# LoraSTM32.net
KiCad netlist of a schematic drawn in Altium Designer
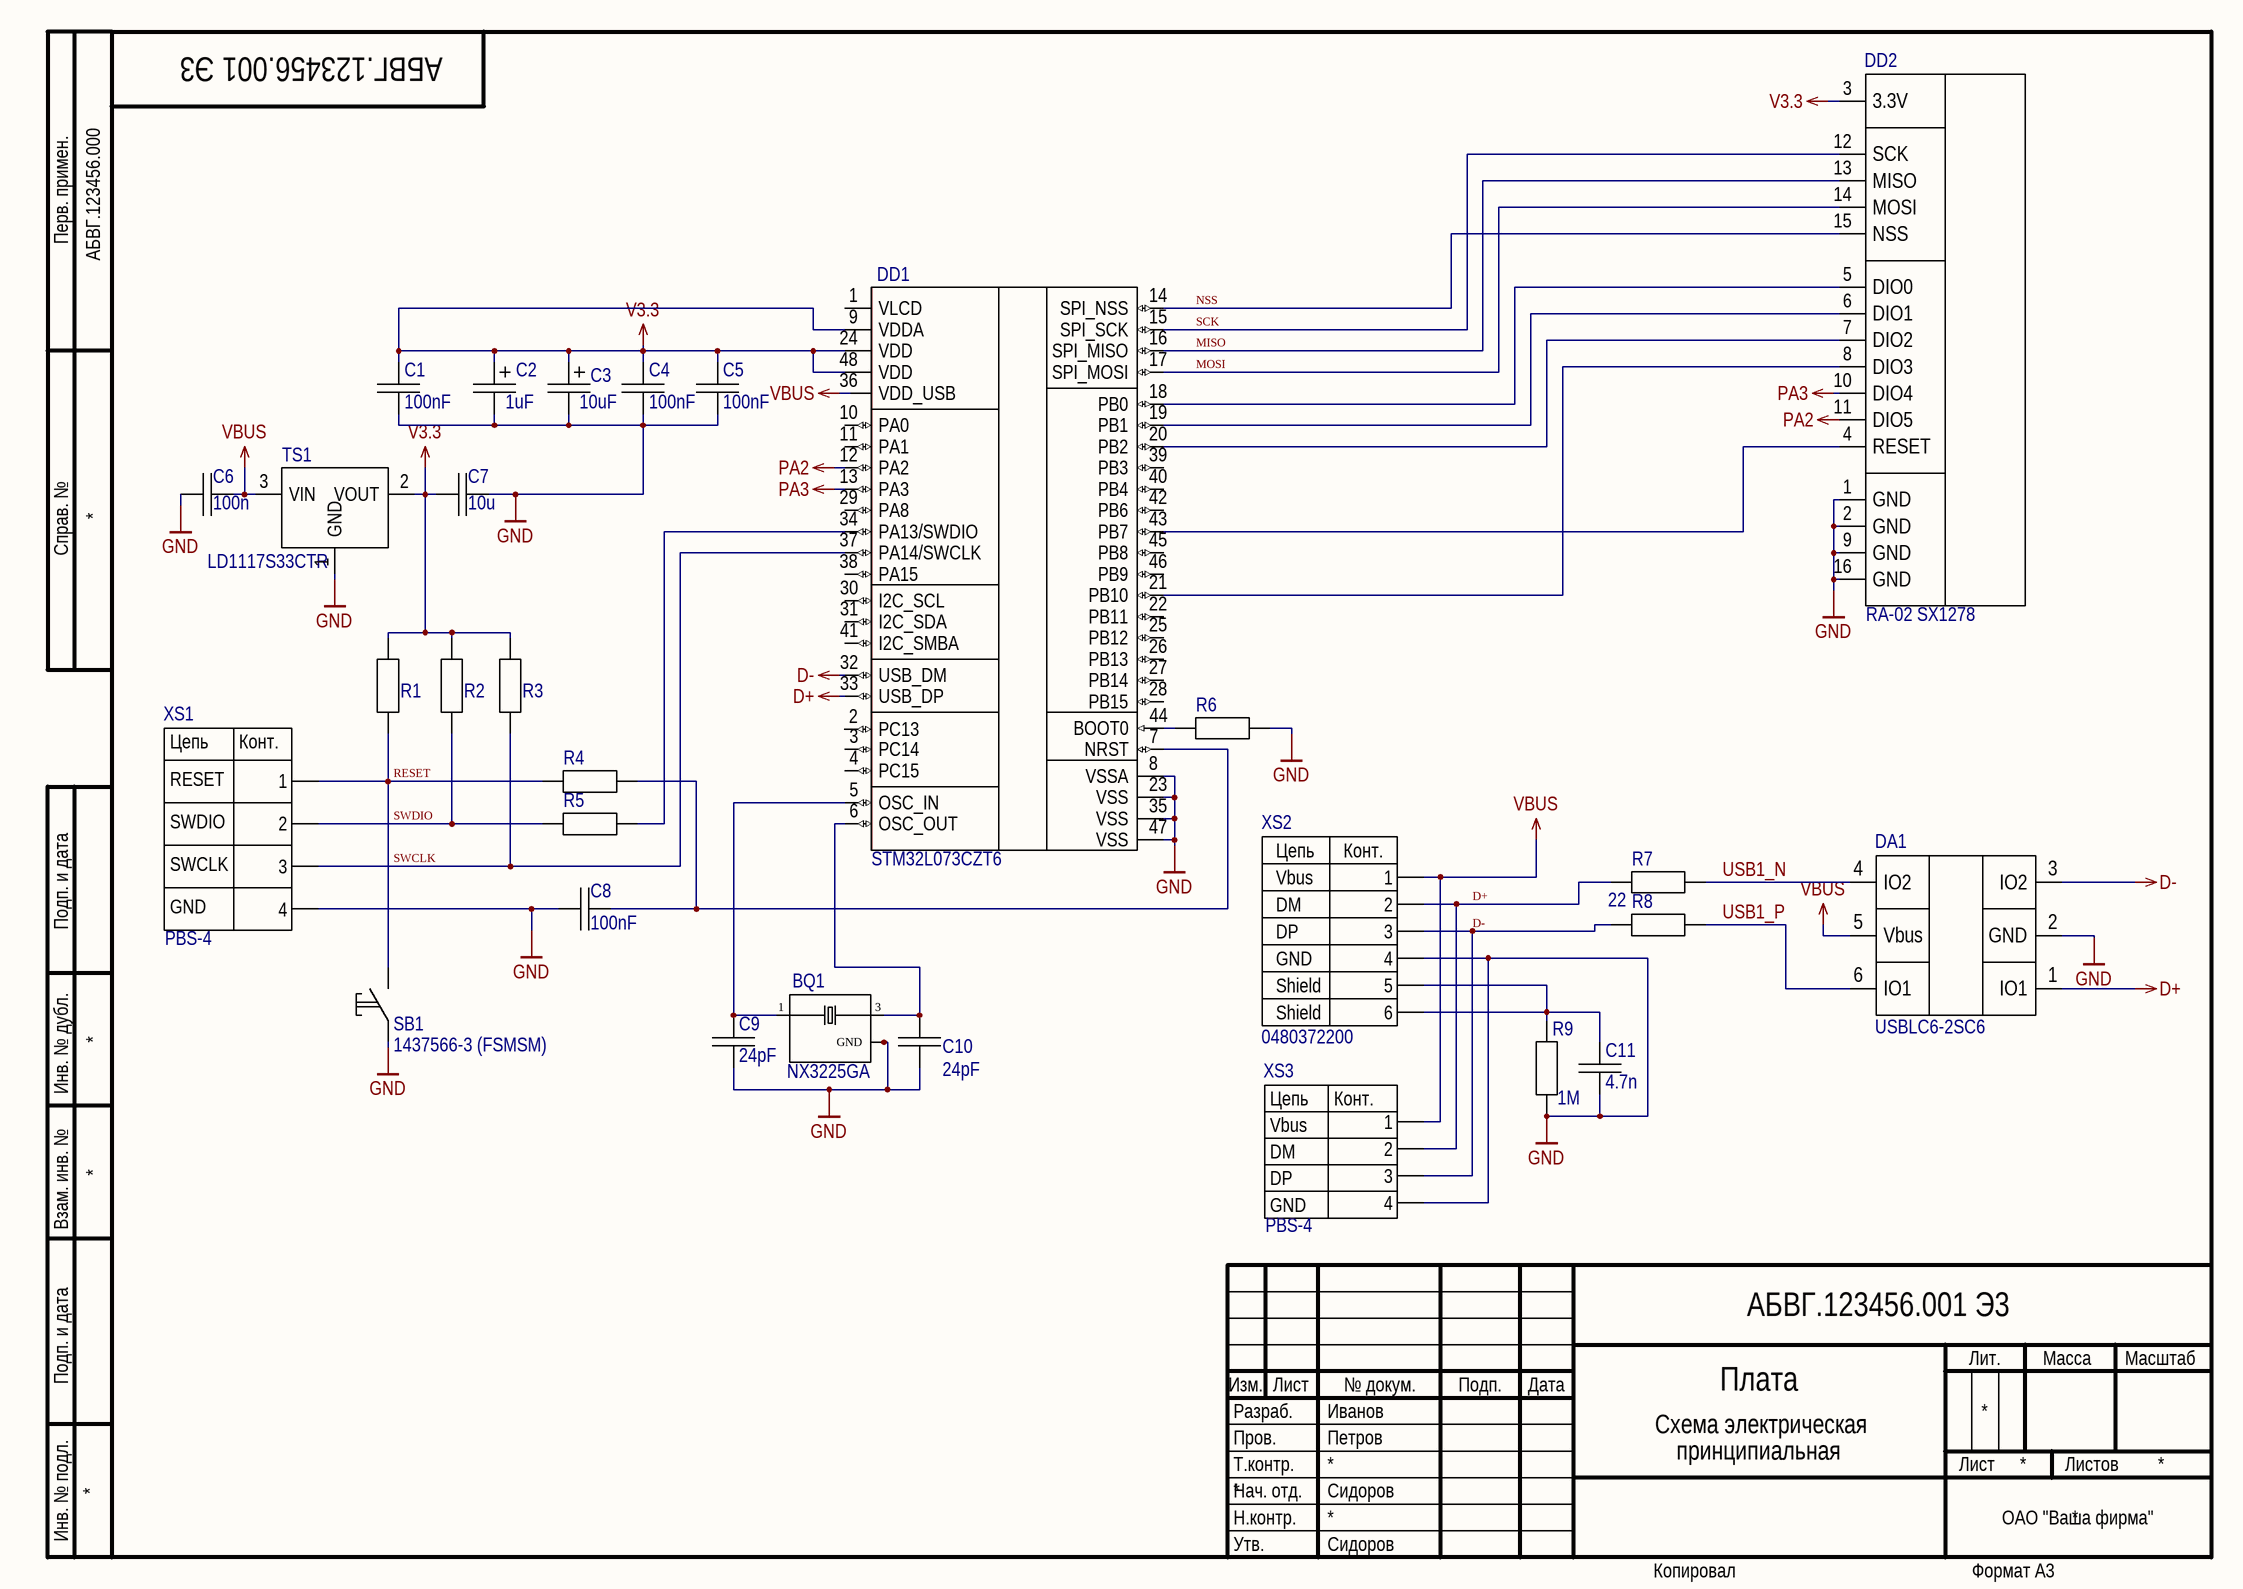
[diagram p0: LoraSTM32.SchDoc]

(export (version "E")
  (design (tool "Eeschema 10.0.6"))
  (components
    (comp (ref "BQ1")
      (value "NX3225GA")
      (footprint "NDK_NX3225GA_0")
      (description "NX3225GA-25MHZ 8pF, 25 МГц, 30/20ppm, 8пФ, -40...+85°C, SMD 3.2*2.5*0.75мм, Кварцевый резонатор")
      (fields (field (name "MF") "NDK America, Inc.") (field (name "MP") "NX3225GA-25MHZ 8pF"))
      (libsource (lib "godnota") (part "NX3225GA-25MHZ"))
    )
    (comp (ref "C1")
      (value "*")
      (footprint "CAPC1608X09L")
      (description "Конденсатор 1.6x0.8 мм")
      (fields (field (name "TOLERANCE") "±10%") (field (name "GRM188R71H104K") "100nF"))
      (libsource (lib "RPSLib") (part "CC1608"))
    )
    (comp (ref "C2")
      (value "*")
      (footprint "CAPMP3216X16N-A")
      (description "Tantalum Surface Mount Capacitor, Size A")
      (fields (field (name "TECAP1/16VA10") "1uF") (field (name "VOLTAGE") "6.3V"))
      (libsource (lib "RPSLib") (part "CT3216-A"))
    )
    (comp (ref "C3")
      (value "*")
      (footprint "CAPMP3216X16N-A")
      (description "Tantalum Surface Mount Capacitor, Size A")
      (fields (field (name "TECAP10/10VA10") "10uF") (field (name "VOLTAGE") "6.3V"))
      (libsource (lib "RPSLib") (part "CT3216-A"))
    )
    (comp (ref "C4")
      (value "GRM188R72A104KA35D")
      (footprint "CAPC1608X09L")
      (description "Конденсатор 1.6x0.8 мм")
      (fields (field (name "TOLERANCE") "±10%") (field (name "GRM188R71H104K") "100nF"))
      (libsource (lib "RPSLib") (part "CC1608"))
    )
    (comp (ref "C5")
      (value "*")
      (footprint "CAPC1608X09L")
      (description "Конденсатор 1.6x0.8 мм")
      (fields (field (name "TOLERANCE") "±10%") (field (name "GRM188R71H104K") "100nF"))
      (libsource (lib "RPSLib") (part "CC1608"))
    )
    (comp (ref "C6")
      (value "*")
      (footprint "CAPC1608X09L")
      (description "Конденсатор 1.6x0.8 мм")
      (fields (field (name "TOLERANCE") "±10%") (field (name "GRM188R71H104K") "100n"))
      (libsource (lib "RPSLib") (part "CC1608"))
    )
    (comp (ref "C7")
      (value "*")
      (footprint "CAPC1608X09L")
      (description "Конденсатор 1.6x0.8 мм")
      (fields (field (name "TOLERANCE") "±10%") (field (name "GRM188R61E106M") "10u"))
      (libsource (lib "RPSLib") (part "CC1608"))
    )
    (comp (ref "C8")
      (value "*")
      (footprint "CAPC1608X09L")
      (description "Конденсатор 1.6x0.8 мм")
      (fields (field (name "TOLERANCE") "±10%") (field (name "GRM188R71H104K") "100nF"))
      (libsource (lib "RPSLib") (part "CC1608"))
    )
    (comp (ref "C9")
      (value "*")
      (footprint "CAPC1608X09L")
      (description "Конденсатор 1.6x0.8 мм")
      (fields (field (name "TOLERANCE") "±10%") (field (name "GRM1885C1H240J") "24pF"))
      (libsource (lib "RPSLib") (part "CC1608"))
    )
    (comp (ref "C10")
      (value "*")
      (footprint "CAPC1608X09L")
      (description "Конденсатор 1.6x0.8 мм")
      (fields (field (name "TOLERANCE") "±10%") (field (name "GRM1887U1H472JA01D") "24pF"))
      (libsource (lib "RPSLib") (part "CC1608"))
    )
    (comp (ref "C11")
      (value "4.7n")
      (footprint "CAPC1608X09L")
      (description "Конденсатор 1.6x0.8 мм")
      (fields (field (name "TOLERANCE") "±10%"))
      (libsource (lib "RPSLib") (part "CC1608"))
    )
    (comp (ref "DA1")
      (value "USBLC6-2SC6")
      (footprint "SOT95P280X145-6N")
      (description "USB protection IC")
      (fields (field (name "MANUFACTURER") "STMicroelectronics"))
      (libsource (lib "RPSLib") (part "USBLC6-2SC6"))
    )
    (comp (ref "DD1")
      (value "STM32L073CZT6")
      (footprint "*QFP50P900X900X160-48N")
      (description "ARMВ® CortexВ®-M0+ STM32 L0 Microcontroller IC 32-Bit 32MHz 192KB _192K x 8_ FLASH 48-LQFP")
      (fields (field (name "MF") "STMicroelectronics") (field (name "DIGI-KEY_PART_NUMBER") "497-17506-ND"))
      (libsource (lib "godnota") (part "STM32L073CZT6"))
    )
    (comp (ref "DD2") (value "RA-02 SX1278") (footprint "RA-02") (libsource (lib "RA-02") (part "RA-02")))
    (comp (ref "R1")
      (value "R1608")
      (footprint "RESC1608X05N")
      (description "Резистор 1.6x0.8 мм")
      (fields (field (name "TOLERANCE") "±1%"))
      (libsource (lib "RPSLib") (part "R1608"))
    )
    (comp (ref "R2")
      (value "R1608")
      (footprint "RESC1608X05N")
      (description "Резистор 1.6x0.8 мм")
      (fields (field (name "TOLERANCE") "±1%"))
      (libsource (lib "RPSLib") (part "R1608"))
    )
    (comp (ref "R3")
      (value "R1608")
      (footprint "RESC1608X05N")
      (description "Резистор 1.6x0.8 мм")
      (fields (field (name "TOLERANCE") "±1%"))
      (libsource (lib "RPSLib") (part "R1608"))
    )
    (comp (ref "R4")
      (value "R1608")
      (footprint "RESC1608X05N")
      (description "Резистор 1.6x0.8 мм")
      (fields (field (name "TOLERANCE") "±1%"))
      (libsource (lib "RPSLib") (part "R1608"))
    )
    (comp (ref "R5")
      (value "R1608")
      (footprint "RESC1608X05N")
      (description "Резистор 1.6x0.8 мм")
      (fields (field (name "TOLERANCE") "±1%"))
      (libsource (lib "RPSLib") (part "R1608"))
    )
    (comp (ref "R6")
      (value "R1608")
      (footprint "RESC1608X05N")
      (description "Резистор 1.6x0.8 мм")
      (fields (field (name "TOLERANCE") "±1%"))
      (libsource (lib "RPSLib") (part "R1608"))
    )
    (comp (ref "R7")
      (value "R1608")
      (footprint "RESC1608X05N")
      (description "Резистор 1.6x0.8 мм")
      (fields (field (name "TOLERANCE") "±1%"))
      (libsource (lib "RPSLib") (part "R1608"))
    )
    (comp (ref "R8")
      (value "22")
      (footprint "RESC1608X05N")
      (description "Резистор 1.6x0.8 мм")
      (fields (field (name "TOLERANCE") "±1%") (field (name "Comment") "R1608"))
      (libsource (lib "RPSLib") (part "R1608"))
    )
    (comp (ref "R9")
      (value "1M")
      (footprint "RESC1608X05N")
      (description "Резистор 1.6x0.8 мм")
      (fields (field (name "TOLERANCE") "±1%") (field (name "Comment") "R1608"))
      (libsource (lib "RPSLib") (part "R1608"))
    )
    (comp (ref "SB1")
      (value "1437566-3 (FSMSM)")
      (footprint "*SW_1437566-4")
      (libsource (lib "godnota") (part "FSMSM"))
    )
    (comp (ref "TS1")
      (value "LD1117S33CTR")
      (footprint "*SOT223")
      (description "Linear Regulator\r\nLDO Regulator Pos 3.3V 1.3A 4-Pin(3+Tab) SOT-223 T/R")
      (libsource (lib "godnota") (part "LD1117S33CTR"))
    )
    (comp (ref "XS1")
      (value "PBS-4")
      (footprint "PBS-4")
      (description "2.54mm swdio")
      (libsource (lib "godnota") (part "отладка swd"))
    )
    (comp (ref "XS2")
      (value "Conn_Molex_0480372200_eec")
      (footprint "Molex_0480372200_0")
      (description "CONN PLUG USB A 4POS SMD R/A")
      (fields
        (field (name "MANUFACTURER") "Molex")
        (field (name "MOUSER PART NUMBER") "538-48037-2200")
        (field (name "PART NUMBER") "0480372200")
      )
      (libsource (lib "Conn_Molex_0480372200_eec") (part "Conn_Molex_0480372200_eec"))
    )
    (comp (ref "XS3")
      (value "PBS-4")
      (footprint "PBS-4")
      (description "2.54mm")
      (libsource (lib "godnota") (part "PBS-4"))
    )
  )
  (nets
    (net (code "1") (name "/MISO") (class "Default")
      (node (ref "DD1") (pin "16") (pinfunction "SPI_MISO_16") (pintype "bidirectional"))
      (node (ref "DD2") (pin "13") (pinfunction "MISO_13") (pintype "passive"))
    )
    (net (code "2") (name "/MOSI") (class "Default")
      (node (ref "DD1") (pin "17") (pinfunction "SPI_MOSI_17") (pintype "bidirectional"))
      (node (ref "DD2") (pin "14") (pinfunction "MOSI_14") (pintype "passive"))
    )
    (net (code "3") (name "/NSS") (class "Default")
      (node (ref "DD1") (pin "14") (pinfunction "SPI_NSS_14") (pintype "bidirectional"))
      (node (ref "DD2") (pin "15") (pinfunction "NSS_15") (pintype "passive"))
    )
    (net (code "4") (name "/RESET") (class "Default")
      (node (ref "R1") (pin "2") (pinfunction "2_2") (pintype "passive"))
      (node (ref "R4") (pin "2") (pinfunction "2_2") (pintype "passive"))
      (node (ref "SB1") (pin "2") (pinfunction "2_2") (pintype "passive"))
      (node (ref "XS1") (pin "1") (pinfunction "1_1") (pintype "passive"))
    )
    (net (code "5") (name "/SCK") (class "Default")
      (node (ref "DD1") (pin "15") (pinfunction "SPI_SCK_15") (pintype "bidirectional"))
      (node (ref "DD2") (pin "12") (pinfunction "SCK_12") (pintype "passive"))
    )
    (net (code "6") (name "/SWCLK") (class "Default")
      (node (ref "DD1") (pin "37") (pinfunction "PA14/SWCLK_37") (pintype "bidirectional"))
      (node (ref "R3") (pin "2") (pinfunction "2_2") (pintype "passive"))
      (node (ref "XS1") (pin "3") (pinfunction "3_3") (pintype "passive"))
    )
    (net (code "7") (name "/SWDIO") (class "Default")
      (node (ref "R2") (pin "2") (pinfunction "2_2") (pintype "passive"))
      (node (ref "R5") (pin "2") (pinfunction "2_2") (pintype "passive"))
      (node (ref "XS1") (pin "2") (pinfunction "2_2") (pintype "passive"))
    )
    (net (code "8") (name "/USB1_N") (class "Default")
      (node (ref "DA1") (pin "4") (pinfunction "IO2_4") (pintype "passive"))
      (node (ref "R7") (pin "1") (pinfunction "1_1") (pintype "passive"))
    )
    (net (code "9") (name "/USB1_P") (class "Default")
      (node (ref "DA1") (pin "6") (pinfunction "IO1_6") (pintype "passive"))
      (node (ref "R8") (pin "1") (pinfunction "1_1") (pintype "passive"))
    )
    (net (code "10") (name "D+") (class "Default")
      (node (ref "DA1") (pin "1") (pinfunction "IO1_1") (pintype "passive"))
      (node (ref "DD1") (pin "33") (pinfunction "USB_DP_33") (pintype "bidirectional"))
      (node (ref "R7") (pin "2") (pinfunction "2_2") (pintype "passive"))
      (node (ref "XS2") (pin "2") (pinfunction "2_2") (pintype "passive"))
      (node (ref "XS3") (pin "2") (pinfunction "2_2") (pintype "passive"))
    )
    (net (code "11") (name "D-") (class "Default")
      (node (ref "DA1") (pin "3") (pinfunction "IO2_3") (pintype "passive"))
      (node (ref "DD1") (pin "32") (pinfunction "USB_DM_32") (pintype "bidirectional"))
      (node (ref "R8") (pin "2") (pinfunction "2_2") (pintype "passive"))
      (node (ref "XS2") (pin "3") (pinfunction "3_3") (pintype "passive"))
      (node (ref "XS3") (pin "3") (pinfunction "3_3") (pintype "passive"))
    )
    (net (code "12") (name "GND") (class "Default")
      (node (ref "BQ1") (pin "2") (pinfunction "GND_2") (pintype "power_in"))
      (node (ref "BQ1") (pin "4") (pinfunction "GND_4") (pintype "power_in"))
      (node (ref "C1") (pin "2") (pinfunction "2_2") (pintype "passive"))
      (node (ref "C10") (pin "1") (pinfunction "1_1") (pintype "passive"))
      (node (ref "C11") (pin "1") (pinfunction "1_1") (pintype "passive"))
      (node (ref "C2") (pin "2") (pinfunction "2_2") (pintype "passive"))
      (node (ref "C3") (pin "2") (pinfunction "2_2") (pintype "passive"))
      (node (ref "C4") (pin "2") (pinfunction "2_2") (pintype "passive"))
      (node (ref "C5") (pin "2") (pinfunction "2_2") (pintype "passive"))
      (node (ref "C6") (pin "2") (pinfunction "2_2") (pintype "passive"))
      (node (ref "C7") (pin "1") (pinfunction "1_1") (pintype "passive"))
      (node (ref "C8") (pin "1") (pinfunction "1_1") (pintype "passive"))
      (node (ref "C9") (pin "1") (pinfunction "1_1") (pintype "passive"))
      (node (ref "DA1") (pin "2") (pinfunction "GND_2") (pintype "passive"))
      (node (ref "DD1") (pin "23") (pinfunction "VSS_23") (pintype "power_in"))
      (node (ref "DD1") (pin "35") (pinfunction "VSS_35") (pintype "power_in"))
      (node (ref "DD1") (pin "47") (pinfunction "VSS_47") (pintype "power_in"))
      (node (ref "DD1") (pin "8") (pinfunction "VSSA_8") (pintype "power_in"))
      (node (ref "DD2") (pin "1") (pinfunction "GND_1") (pintype "passive"))
      (node (ref "DD2") (pin "16") (pinfunction "GND_16") (pintype "passive"))
      (node (ref "DD2") (pin "2") (pinfunction "GND_2") (pintype "passive"))
      (node (ref "DD2") (pin "9") (pinfunction "GND_9") (pintype "passive"))
      (node (ref "R6") (pin "1") (pinfunction "1_1") (pintype "passive"))
      (node (ref "R9") (pin "1") (pinfunction "1_1") (pintype "passive"))
      (node (ref "SB1") (pin "1") (pinfunction "1_1") (pintype "passive"))
      (node (ref "TS1") (pin "1") (pinfunction "GND_1") (pintype "power_in"))
      (node (ref "XS1") (pin "4") (pinfunction "4_4") (pintype "passive"))
      (node (ref "XS2") (pin "4") (pinfunction "4_4") (pintype "passive"))
      (node (ref "XS3") (pin "4") (pinfunction "4_4") (pintype "passive"))
    )
    (net (code "13") (name "Net-(DD1-BOOT0)") (class "Default")
      (node (ref "DD1") (pin "44") (pinfunction "BOOT0_44") (pintype "input"))
      (node (ref "R6") (pin "2") (pinfunction "2_2") (pintype "passive"))
    )
    (net (code "14") (name "Net-(DD1-NRST)") (class "Default")
      (node (ref "C8") (pin "2") (pinfunction "2_2") (pintype "passive"))
      (node (ref "DD1") (pin "7") (pinfunction "NRST_7") (pintype "bidirectional"))
      (node (ref "R4") (pin "1") (pinfunction "1_1") (pintype "passive"))
    )
    (net (code "15") (name "Net-(DD1-OSC_IN)") (class "Default")
      (node (ref "BQ1") (pin "1") (pinfunction "1_1") (pintype "passive"))
      (node (ref "C9") (pin "2") (pinfunction "2_2") (pintype "passive"))
      (node (ref "DD1") (pin "5") (pinfunction "OSC_IN_5") (pintype "bidirectional"))
    )
    (net (code "16") (name "Net-(DD1-OSC_OUT)") (class "Default")
      (node (ref "BQ1") (pin "3") (pinfunction "3_3") (pintype "passive"))
      (node (ref "C10") (pin "2") (pinfunction "2_2") (pintype "passive"))
      (node (ref "DD1") (pin "6") (pinfunction "OSC_OUT_6") (pintype "bidirectional"))
    )
    (net (code "17") (name "Net-(DD1-PA13{slash}SWDIO)") (class "Default")
      (node (ref "DD1") (pin "34") (pinfunction "PA13/SWDIO_34") (pintype "bidirectional"))
      (node (ref "R5") (pin "1") (pinfunction "1_1") (pintype "passive"))
    )
    (net (code "18") (name "Net-(DD1-PB0)") (class "Default")
      (node (ref "DD1") (pin "18") (pinfunction "PB0_18") (pintype "bidirectional"))
      (node (ref "DD2") (pin "5") (pinfunction "DIO0_5") (pintype "passive"))
    )
    (net (code "19") (name "Net-(DD1-PB1)") (class "Default")
      (node (ref "DD1") (pin "19") (pinfunction "PB1_19") (pintype "bidirectional"))
      (node (ref "DD2") (pin "6") (pinfunction "DIO1_6") (pintype "passive"))
    )
    (net (code "20") (name "Net-(DD1-PB2)") (class "Default")
      (node (ref "DD1") (pin "20") (pinfunction "PB2_20") (pintype "bidirectional"))
      (node (ref "DD2") (pin "7") (pinfunction "DIO2_7") (pintype "passive"))
    )
    (net (code "21") (name "Net-(DD1-PB7)") (class "Default")
      (node (ref "DD1") (pin "43") (pinfunction "PB7_43") (pintype "bidirectional"))
      (node (ref "DD2") (pin "4") (pinfunction "RESET_4") (pintype "passive"))
    )
    (net (code "22") (name "Net-(DD1-PB10)") (class "Default")
      (node (ref "DD1") (pin "21") (pinfunction "PB10_21") (pintype "bidirectional"))
      (node (ref "DD2") (pin "8") (pinfunction "DIO3_8") (pintype "passive"))
    )
    (net (code "23") (name "Net-(XS2-MNT_1)") (class "Default")
      (node (ref "C11") (pin "2") (pinfunction "2_2") (pintype "passive"))
      (node (ref "R9") (pin "2") (pinfunction "2_2") (pintype "passive"))
      (node (ref "XS2") (pin "5") (pinfunction "MNT_1_5") (pintype "passive"))
      (node (ref "XS2") (pin "6") (pinfunction "MNT_2_6") (pintype "passive"))
    )
    (net (code "24") (name "PA2") (class "Default")
      (node (ref "DD1") (pin "12") (pinfunction "PA2_12") (pintype "bidirectional"))
      (node (ref "DD2") (pin "11") (pinfunction "DIO5_11") (pintype "passive"))
    )
    (net (code "25") (name "PA3") (class "Default")
      (node (ref "DD1") (pin "13") (pinfunction "PA3_13") (pintype "bidirectional"))
      (node (ref "DD2") (pin "10") (pinfunction "DIO4_10") (pintype "passive"))
    )
    (net (code "26") (name "V3.3") (class "Default")
      (node (ref "C1") (pin "1") (pinfunction "1_1") (pintype "passive"))
      (node (ref "C2") (pin "1") (pinfunction "1_1") (pintype "passive"))
      (node (ref "C3") (pin "1") (pinfunction "1_1") (pintype "passive"))
      (node (ref "C4") (pin "1") (pinfunction "1_1") (pintype "passive"))
      (node (ref "C5") (pin "1") (pinfunction "1_1") (pintype "passive"))
      (node (ref "C7") (pin "2") (pinfunction "2_2") (pintype "passive"))
      (node (ref "DD1") (pin "24") (pinfunction "VDD_24") (pintype "power_in"))
      (node (ref "DD1") (pin "48") (pinfunction "VDD_48") (pintype "power_in"))
      (node (ref "DD1") (pin "9") (pinfunction "VDDA_9") (pintype "power_in"))
      (node (ref "DD2") (pin "3") (pinfunction "3.3V_3") (pintype "passive"))
      (node (ref "R1") (pin "1") (pinfunction "1_1") (pintype "passive"))
      (node (ref "R2") (pin "1") (pinfunction "1_1") (pintype "passive"))
      (node (ref "R3") (pin "1") (pinfunction "1_1") (pintype "passive"))
      (node (ref "TS1") (pin "2") (pinfunction "VOUT_2") (pintype "power_in"))
    )
    (net (code "27") (name "VBUS") (class "Default")
      (node (ref "C6") (pin "1") (pinfunction "1_1") (pintype "passive"))
      (node (ref "DA1") (pin "5") (pinfunction "Vbus_5") (pintype "passive"))
      (node (ref "DD1") (pin "36") (pinfunction "VDD_USB_36") (pintype "power_in"))
      (node (ref "TS1") (pin "3") (pinfunction "VIN_3") (pintype "power_in"))
      (node (ref "XS2") (pin "1") (pinfunction "1_1") (pintype "passive"))
      (node (ref "XS3") (pin "1") (pinfunction "1_1") (pintype "passive"))
    )
    (net (code "28") (name "unconnected-(DD1-I2C_SCL-Pad30)") (class "Default")
      (node (ref "DD1") (pin "30") (pinfunction "I2C_SCL_30") (pintype "bidirectional"))
    )
    (net (code "29") (name "unconnected-(DD1-I2C_SDA-Pad31)") (class "Default")
      (node (ref "DD1") (pin "31") (pinfunction "I2C_SDA_31") (pintype "bidirectional"))
    )
    (net (code "30") (name "unconnected-(DD1-I2C_SMBA-Pad41)") (class "Default")
      (node (ref "DD1") (pin "41") (pinfunction "I2C_SMBA_41") (pintype "bidirectional"))
    )
    (net (code "31") (name "unconnected-(DD1-PA0-Pad10)") (class "Default")
      (node (ref "DD1") (pin "10") (pinfunction "PA0_10") (pintype "bidirectional"))
    )
    (net (code "32") (name "unconnected-(DD1-PA1-Pad11)") (class "Default")
      (node (ref "DD1") (pin "11") (pinfunction "PA1_11") (pintype "bidirectional"))
    )
    (net (code "33") (name "unconnected-(DD1-PA8-Pad29)") (class "Default")
      (node (ref "DD1") (pin "29") (pinfunction "PA8_29") (pintype "bidirectional"))
    )
    (net (code "34") (name "unconnected-(DD1-PA15-Pad38)") (class "Default")
      (node (ref "DD1") (pin "38") (pinfunction "PA15_38") (pintype "bidirectional"))
    )
    (net (code "35") (name "unconnected-(DD1-PB3-Pad39)") (class "Default")
      (node (ref "DD1") (pin "39") (pinfunction "PB3_39") (pintype "bidirectional"))
    )
    (net (code "36") (name "unconnected-(DD1-PB4-Pad40)") (class "Default")
      (node (ref "DD1") (pin "40") (pinfunction "PB4_40") (pintype "bidirectional"))
    )
    (net (code "37") (name "unconnected-(DD1-PB6-Pad42)") (class "Default")
      (node (ref "DD1") (pin "42") (pinfunction "PB6_42") (pintype "bidirectional"))
    )
    (net (code "38") (name "unconnected-(DD1-PB8-Pad45)") (class "Default")
      (node (ref "DD1") (pin "45") (pinfunction "PB8_45") (pintype "bidirectional"))
    )
    (net (code "39") (name "unconnected-(DD1-PB9-Pad46)") (class "Default")
      (node (ref "DD1") (pin "46") (pinfunction "PB9_46") (pintype "bidirectional"))
    )
    (net (code "40") (name "unconnected-(DD1-PB11-Pad22)") (class "Default")
      (node (ref "DD1") (pin "22") (pinfunction "PB11_22") (pintype "bidirectional"))
    )
    (net (code "41") (name "unconnected-(DD1-PB12-Pad25)") (class "Default")
      (node (ref "DD1") (pin "25") (pinfunction "PB12_25") (pintype "bidirectional"))
    )
    (net (code "42") (name "unconnected-(DD1-PB13-Pad26)") (class "Default")
      (node (ref "DD1") (pin "26") (pinfunction "PB13_26") (pintype "bidirectional"))
    )
    (net (code "43") (name "unconnected-(DD1-PB14-Pad27)") (class "Default")
      (node (ref "DD1") (pin "27") (pinfunction "PB14_27") (pintype "bidirectional"))
    )
    (net (code "44") (name "unconnected-(DD1-PB15-Pad28)") (class "Default")
      (node (ref "DD1") (pin "28") (pinfunction "PB15_28") (pintype "bidirectional"))
    )
    (net (code "45") (name "unconnected-(DD1-PC13-Pad2)") (class "Default")
      (node (ref "DD1") (pin "2") (pinfunction "PC13_2") (pintype "bidirectional"))
    )
    (net (code "46") (name "unconnected-(DD1-PC14-Pad3)") (class "Default")
      (node (ref "DD1") (pin "3") (pinfunction "PC14_3") (pintype "bidirectional"))
    )
    (net (code "47") (name "unconnected-(DD1-PC15-Pad4)") (class "Default")
      (node (ref "DD1") (pin "4") (pinfunction "PC15_4") (pintype "bidirectional"))
    )
    (net (code "48") (name "unconnected-(DD1-VLCD-Pad1)") (class "Default")
      (node (ref "DD1") (pin "1") (pinfunction "VLCD_1") (pintype "power_in"))
    )
  )
)
